# STLINKv2DIY.net
KiCad netlist of a schematic drawn in Altium Designer
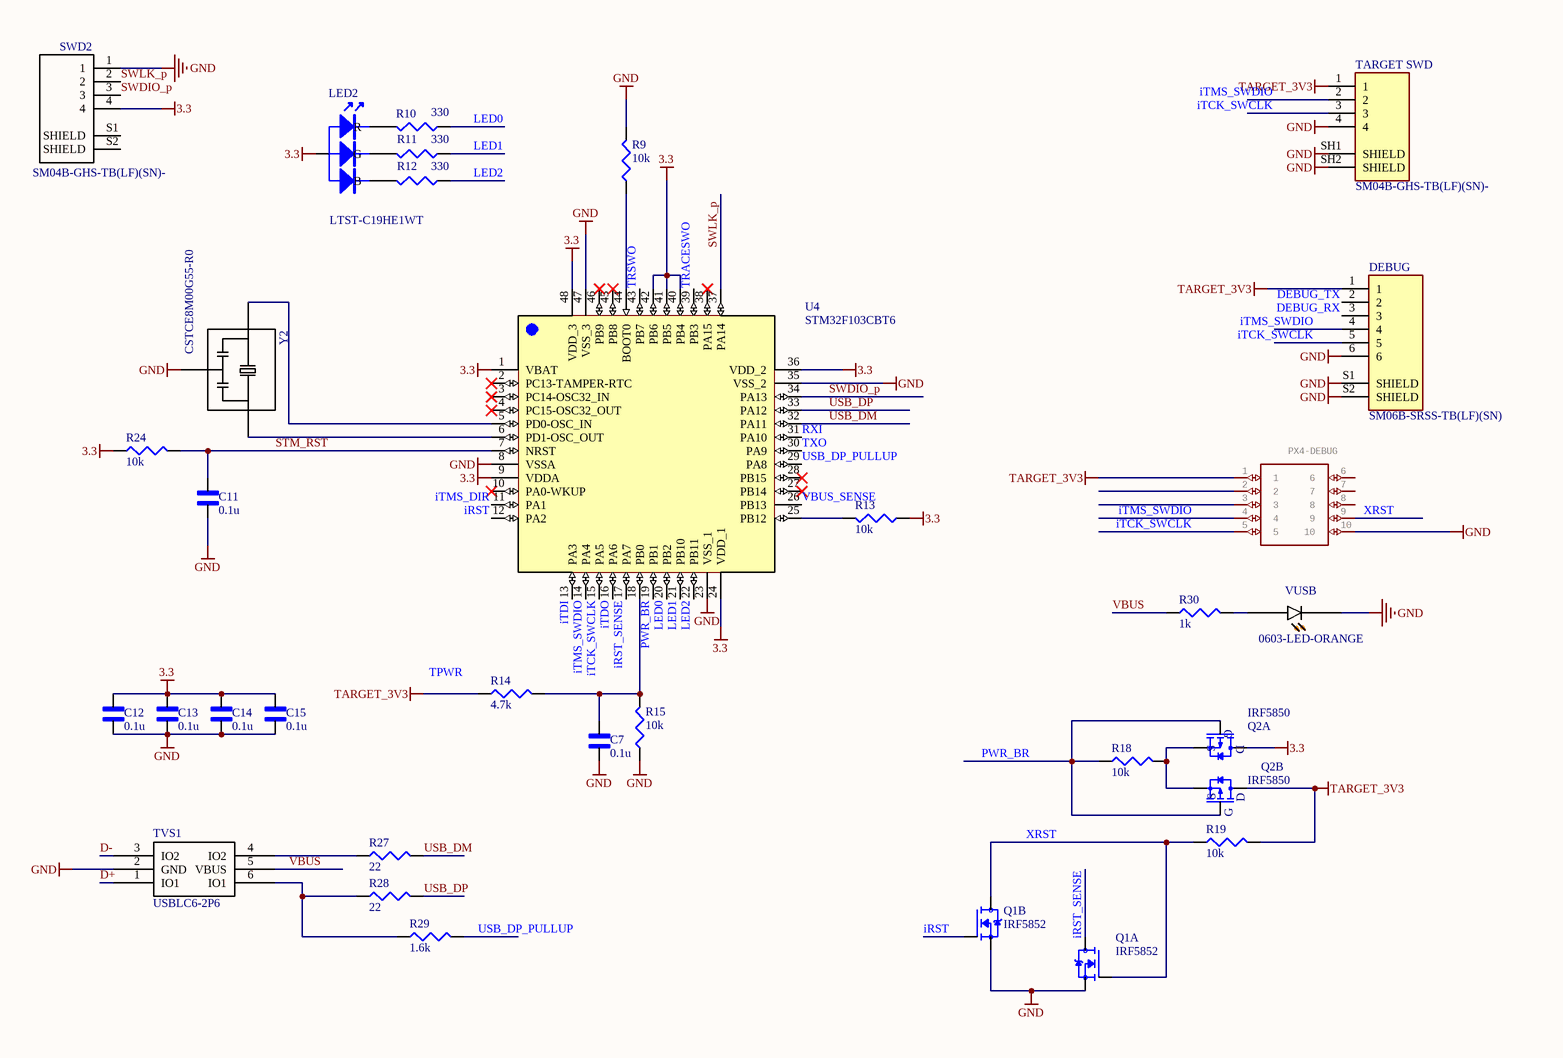
[diagram p0: STLINKv2DIY.SchDoc]

(export (version "E")
  (design (tool "Eeschema 10.0.6"))
  (components
    (comp (ref "C7")
      (value "0.1u")
      (footprint "CAPC1005X55N")
      (description "GCM155R71H104KE02D, Чип 0402 X7R 0.1uF +10% 50V,Конденсатор")
      (fields (field (name "MF") "Murata") (field (name "MP") "GCM155R71H104KE02D"))
      (libsource (lib "lib") (part "GCM155R71H104KE02D"))
    )
    (comp (ref "C11")
      (value "0.1u")
      (footprint "CAPC1005X55N")
      (description "GCM155R71H104KE02D, Чип 0402 X7R 0.1uF +10% 50V,Конденсатор")
      (fields (field (name "MF") "Murata") (field (name "MP") "GCM155R71H104KE02D"))
      (libsource (lib "lib") (part "GCM155R71H104KE02D"))
    )
    (comp (ref "C12")
      (value "0.1u")
      (footprint "CAPC1005X55N")
      (description "GCM155R71H104KE02D, Чип 0402 X7R 0.1uF +10% 50V,Конденсатор")
      (fields (field (name "MF") "Murata") (field (name "MP") "GCM155R71H104KE02D"))
      (libsource (lib "lib") (part "GCM155R71H104KE02D"))
    )
    (comp (ref "C13")
      (value "0.1u")
      (footprint "CAPC1005X55N")
      (description "GCM155R71H104KE02D, Чип 0402 X7R 0.1uF +10% 50V,Конденсатор")
      (fields (field (name "MF") "Murata") (field (name "MP") "GCM155R71H104KE02D"))
      (libsource (lib "lib") (part "GCM155R71H104KE02D"))
    )
    (comp (ref "C14")
      (value "0.1u")
      (footprint "CAPC1005X55N")
      (description "GCM155R71H104KE02D, Чип 0402 X7R 0.1uF +10% 50V,Конденсатор")
      (fields (field (name "MF") "Murata") (field (name "MP") "GCM155R71H104KE02D"))
      (libsource (lib "lib") (part "GCM155R71H104KE02D"))
    )
    (comp (ref "C15")
      (value "0.1u")
      (footprint "CAPC1005X55N")
      (description "GCM155R71H104KE02D, Чип 0402 X7R 0.1uF +10% 50V,Конденсатор")
      (fields (field (name "MF") "Murata") (field (name "MP") "GCM155R71H104KE02D"))
      (libsource (lib "lib") (part "GCM155R71H104KE02D"))
    )
    (comp (ref "DEBUG")
      (value "SM06B-SRSS-TB(LF)(SN)")
      (footprint "JST_SM06B-SRSS-TB(LF)(SN)")
      (description "Connector Header Surface Mount, Right Angle 6 position 0.039 _1.00mm_")
      (fields (field (name "MP") "SM06B-SRSS-TB_LF__SN_") (field (name "MF") "JST Sales"))
      (libsource (lib "lib") (part "SM06B-SRSS-TB(LF)(SN)"))
    )
    (comp (ref "LED2")
      (value "LTST-C19HE1WT")
      (footprint "LTST-C19HE1WT")
      (description "Blue/Green/Red")
      (libsource (lib "lib") (part "RGB_LED_5MM"))
    )
    (comp (ref "PX4-DEBUG")
      (value "JST (JAPAN SOLDERLESS TERMINALS) - SM10B-SRSS-TB(LF)(SN) - HEADER, R/A, 10WAY   Source:  Datasheet")
      (footprint "SM10B-SRSS-TB")
      (fields
        (field (name "MANUFACTURER_PART_NUMBER") "SM10B-SRSS-TB(LF)(SN)")
        (field (name "MP") "SM10B-SRSS-TB")
        (field (name "MF") "JST Sales")
      )
      (libsource (lib "lib") (part "SM10B-SRSS-TB_LF__SN_"))
    )
    (comp (ref "Q1")
      (value "IRF5852")
      (footprint "SOT23-6")
      (description "Mosfet Array 2 N-Channel _Dual_ 20V 2.7A 960mW Surface Mount 6-TSOP")
      (fields (field (name "MF") "Infineon"))
      (libsource (lib "") (part "IRF5852_1"))
    )
    (comp (ref "Q2")
      (value "IRF5850")
      (footprint "SOT23-6")
      (description "Mosfet Array 2 P-Channel (Dual) 20V 2.2A 960mW Surface Mount 6-TSOP")
      (fields (field (name "MF") "Infineon"))
      (libsource (lib "lib") (part "IRF5850"))
    )
    (comp (ref "R9")
      (value "10k")
      (footprint "RESC1005X40N")
      (description "0.062Вт 0402 10 кОм, 1%, Чип резистор (SMD)")
      (fields (field (name "MF") "Yageo or NXP") (field (name "MP") "RC0402FR-0710KL"))
      (libsource (lib "lib") (part "RC0402FR-0710KL"))
    )
    (comp (ref "R10")
      (value "330")
      (footprint "RESC1005X40N")
      (description "0.062Вт 0402 330 Ом, 1%, Чип резистор (SMD)")
      (fields (field (name "MF") "Yageo or NXP") (field (name "MP") "RC0402FR-07330RL"))
      (libsource (lib "lib") (part "RC0402FR-07330RL"))
    )
    (comp (ref "R11")
      (value "330")
      (footprint "RESC1005X40N")
      (description "0.062Вт 0402 330 Ом, 1%, Чип резистор (SMD)")
      (fields (field (name "MF") "Yageo or NXP") (field (name "MP") "RC0402FR-07330RL"))
      (libsource (lib "lib") (part "RC0402FR-07330RL"))
    )
    (comp (ref "R12")
      (value "330")
      (footprint "RESC1005X40N")
      (description "0.062Вт 0402 330 Ом, 1%, Чип резистор (SMD)")
      (fields (field (name "MF") "Yageo or NXP") (field (name "MP") "RC0402FR-07330RL"))
      (libsource (lib "lib") (part "RC0402FR-07330RL"))
    )
    (comp (ref "R13")
      (value "10k")
      (footprint "RESC1005X40N")
      (description "0.062Вт 0402 10 кОм, 1%, Чип резистор (SMD)")
      (fields (field (name "MF") "Yageo or NXP") (field (name "MP") "RC0402FR-0710KL"))
      (libsource (lib "lib") (part "RC0402FR-0710KL"))
    )
    (comp (ref "R14")
      (value "4.7k")
      (footprint "RESC1005X40N")
      (description "0.062Вт 0402 4.7 кОм, 1%, Чип резистор (SMD)")
      (fields (field (name "MF") "Yageo or NXP") (field (name "MP") "RC0402FR-074K7L"))
      (libsource (lib "lib") (part "RC0402FR-074K7L"))
    )
    (comp (ref "R15")
      (value "10k")
      (footprint "RESC1005X40N")
      (description "0.062Вт 0402 10 кОм, 1%, Чип резистор (SMD)")
      (fields (field (name "MF") "Yageo or NXP") (field (name "MP") "RC0402FR-0710KL"))
      (libsource (lib "lib") (part "RC0402FR-0710KL"))
    )
    (comp (ref "R18")
      (value "10k")
      (footprint "RESC1005X40N")
      (description "0.062Вт 0402 10 кОм, 1%, Чип резистор (SMD)")
      (fields (field (name "MF") "Yageo or NXP") (field (name "MP") "RC0402FR-0710KL"))
      (libsource (lib "lib") (part "RC0402FR-0710KL"))
    )
    (comp (ref "R19")
      (value "10k")
      (footprint "RESC1005X40N")
      (description "0.062Вт 0402 10 кОм, 1%, Чип резистор (SMD)")
      (fields (field (name "MF") "Yageo or NXP") (field (name "MP") "RC0402FR-0710KL"))
      (libsource (lib "lib") (part "RC0402FR-0710KL"))
    )
    (comp (ref "R24")
      (value "10k")
      (footprint "RESC1005X40N")
      (description "0.062Вт 0402 10 кОм, 1%, Чип резистор (SMD)")
      (fields (field (name "MF") "Yageo or NXP") (field (name "MP") "RC0402FR-0710KL"))
      (libsource (lib "lib") (part "RC0402FR-0710KL"))
    )
    (comp (ref "R27")
      (value "22")
      (footprint "RESC1005X40N")
      (description "0.062Вт 0402 22 Ом, 1%, Чип резистор (SMD)")
      (fields (field (name "MF") "Yageo or NXP") (field (name "MP") "RC0402FR-0722RL"))
      (libsource (lib "lib") (part "RC0402FR-0722RL"))
    )
    (comp (ref "R28")
      (value "22")
      (footprint "RESC1005X40N")
      (description "0.062Вт 0402 22 Ом, 1%, Чип резистор (SMD)")
      (fields (field (name "MF") "Yageo or NXP") (field (name "MP") "RC0402FR-0722RL"))
      (libsource (lib "lib") (part "RC0402FR-0722RL"))
    )
    (comp (ref "R29")
      (value "1.6k")
      (footprint "RESC1005X40N")
      (description "0.062Вт 0402 1.6 кОм, 1%, Чип резистор (SMD)")
      (fields (field (name "MF") "Yageo or NXP") (field (name "MP") "RC0402FR-071K6L"))
      (libsource (lib "lib") (part "RC0402FR-071K6L"))
    )
    (comp (ref "R30")
      (value "1k")
      (footprint "RESC1005X40N")
      (description "0.062Вт 0402 1 кОм, 1%, Чип резистор (SMD)")
      (fields (field (name "MF") "Yageo or NXP") (field (name "MP") "RC0402FR-071KL"))
      (libsource (lib "lib") (part "RC0402FR-071KL"))
    )
    (comp (ref "SWD2")
      (value "SM04B-GHS-TB(LF)(SN)-")
      (footprint "JST_BM04B-GHS-holes")
      (description "Conn Shrouded Header HDR 4 POS 1.25mm Solder ST SMD Reel")
      (fields (field (name "MF") "JST Sales") (field (name "MP") "SM04B-GHS-TB(LF)(SN)"))
      (libsource (lib "lib") (part "SWD SM04B-GHS-TB(LF)(SN)-"))
    )
    (comp (ref "TARGET SWD")
      (value "SM04B-GHS-TB(LF)(SN)-")
      (footprint "JST_SM04B-GHS-TB(LF)(SN)-")
      (description "Connector Header Surface Mount, Right Angle 4 position 0.049 _1.25mm_")
      (fields (field (name "MP") "SM04B-GHS-TB(LF)(SN)") (field (name "MF") "JST Sales"))
      (libsource (lib "lib") (part "SM04B-GHS-TB(LF)(SN)-"))
    )
    (comp (ref "TVS1")
      (value "USBLC6-2P6")
      (footprint "SOT23127P600-8N")
      (description "17V Clamp 5A (8/20µs) Ipp Tvs Diode Surface Mount SOT-666")
      (fields (field (name "MF") "STM"))
      (libsource (lib "lib") (part "USBLC6-2P6"))
    )
    (comp (ref "U4")
      (value "STM32F103CBT6")
      (footprint "STM-LQFP48_N")
      (description "ARM® Cortex®-M3 STM32F1 Microcontroller IC 32-Bit 72MHz 128KB (128K x 8) FLASH")
      (fields (field (name "MF") "STM"))
      (libsource (lib "lib") (part "STM32F103CBT6"))
    )
    (comp (ref "VUSB")
      (value "0603-LED-ORANGE")
      (footprint "*LEDM1608X80_LTE-C1906R-14(Primary)")
      (description "Orange 605nm LED Indication - Discrete 2.2V 0603 (1608 Metric)")
      (fields (field (name "MP") "LTST-C194KFKT"))
      (libsource (lib "lib") (part "0603-LED-ORANGE"))
    )
    (comp (ref "Y2")
      (value "CSTCE8M00G55-R0")
      (footprint "*OSC_CSTCE8M00G55-R0")
      (description "Ceramic Resonator 8MHz ??0.5% _Tol_ ??0.2% _Stability_ 33pF 40Ohm 3-Pin CSMD T/R")
      (fields (field (name "MF") "Murata"))
      (libsource (lib "lib") (part "CSTCE8M00G55-R0"))
    )
  )
  (nets
    (net (code "1") (name "/D+") (class "Default")
      (node (ref "TVS1") (pin "1") (pinfunction "IO1_1") (pintype "passive"))
    )
    (net (code "2") (name "/D-") (class "Default")
      (node (ref "TVS1") (pin "3") (pinfunction "IO2_3") (pintype "passive"))
    )
    (net (code "3") (name "/DEBUG_RX") (class "Default")
      (node (ref "DEBUG") (pin "3") (pinfunction "3_3") (pintype "passive"))
    )
    (net (code "4") (name "/DEBUG_TX") (class "Default")
      (node (ref "DEBUG") (pin "2") (pinfunction "2_2") (pintype "passive"))
    )
    (net (code "5") (name "/LED0") (class "Default")
      (node (ref "R10") (pin "1") (pinfunction "1_1") (pintype "passive"))
      (node (ref "U4") (pin "20") (pinfunction "PB2_20") (pintype "bidirectional"))
    )
    (net (code "6") (name "/LED1") (class "Default")
      (node (ref "R11") (pin "1") (pinfunction "1_1") (pintype "passive"))
      (node (ref "U4") (pin "21") (pinfunction "PB10_21") (pintype "bidirectional"))
    )
    (net (code "7") (name "/LED2") (class "Default")
      (node (ref "R12") (pin "1") (pinfunction "1_1") (pintype "passive"))
      (node (ref "U4") (pin "22") (pinfunction "PB11_22") (pintype "bidirectional"))
    )
    (net (code "8") (name "/PWR_BR") (class "Default")
      (node (ref "Q2") (pin "1") (pinfunction "G_1") (pintype "passive"))
      (node (ref "Q2") (pin "3") (pinfunction "G_3") (pintype "passive"))
      (node (ref "R18") (pin "1") (pinfunction "1_1") (pintype "passive"))
      (node (ref "U4") (pin "19") (pinfunction "PB1_19") (pintype "bidirectional"))
    )
    (net (code "9") (name "/RXI") (class "Default")
      (node (ref "U4") (pin "31") (pinfunction "PA10_31") (pintype "bidirectional"))
    )
    (net (code "10") (name "/STM_RST") (class "Default")
      (node (ref "C11") (pin "2") (pinfunction "2_2") (pintype "passive"))
      (node (ref "R24") (pin "2") (pinfunction "2_2") (pintype "passive"))
      (node (ref "U4") (pin "7") (pinfunction "NRST_7") (pintype "bidirectional"))
    )
    (net (code "11") (name "/SWDIO_p") (class "Default")
      (node (ref "SWD2") (pin "3") (pinfunction "3_3") (pintype "passive"))
      (node (ref "U4") (pin "34") (pinfunction "PA13_34") (pintype "bidirectional"))
    )
    (net (code "12") (name "/SWLK_p") (class "Default")
      (node (ref "SWD2") (pin "2") (pinfunction "2_2") (pintype "passive"))
      (node (ref "U4") (pin "37") (pinfunction "PA14_37") (pintype "bidirectional"))
    )
    (net (code "14") (name "/TRACESWO") (class "Default")
      (node (ref "U4") (pin "39") (pinfunction "PB3_39") (pintype "bidirectional"))
    )
    (net (code "15") (name "/TRSWO") (class "Default")
      (node (ref "U4") (pin "43") (pinfunction "PB7_43") (pintype "bidirectional"))
    )
    (net (code "16") (name "/TXO") (class "Default")
      (node (ref "U4") (pin "30") (pinfunction "PA9_30") (pintype "bidirectional"))
    )
    (net (code "17") (name "/USB_DM") (class "Default")
      (node (ref "R27") (pin "2") (pinfunction "2_2") (pintype "passive"))
      (node (ref "U4") (pin "32") (pinfunction "PA11_32") (pintype "bidirectional"))
    )
    (net (code "18") (name "/USB_DP") (class "Default")
      (node (ref "R28") (pin "2") (pinfunction "2_2") (pintype "passive"))
      (node (ref "U4") (pin "33") (pinfunction "PA12_33") (pintype "bidirectional"))
    )
    (net (code "19") (name "/USB_DP_PULLUP") (class "Default")
      (node (ref "R29") (pin "2") (pinfunction "2_2") (pintype "passive"))
      (node (ref "U4") (pin "29") (pinfunction "PA8_29") (pintype "bidirectional"))
    )
    (net (code "20") (name "/VBUS") (class "Default")
      (node (ref "R30") (pin "1") (pinfunction "1_1") (pintype "passive"))
      (node (ref "TVS1") (pin "5") (pinfunction "VBUS_5") (pintype "passive"))
    )
    (net (code "21") (name "/VBUS_SENSE") (class "Default")
      (node (ref "U4") (pin "26") (pinfunction "PB13_26") (pintype "power_in"))
    )
    (net (code "22") (name "/XRST") (class "Default")
      (node (ref "PX4-DEBUG") (pin "9") (pinfunction "9_9") (pintype "bidirectional"))
      (node (ref "Q1") (pin "1") (pinfunction "G_1") (pintype "passive"))
      (node (ref "Q1") (pin "4") (pinfunction "D_4") (pintype "passive"))
      (node (ref "R19") (pin "1") (pinfunction "1_1") (pintype "passive"))
    )
    (net (code "23") (name "/iRST") (class "Default")
      (node (ref "Q1") (pin "3") (pinfunction "G_3") (pintype "passive"))
      (node (ref "U4") (pin "12") (pinfunction "PA2_12") (pintype "bidirectional"))
    )
    (net (code "24") (name "/iRST_SENSE") (class "Default")
      (node (ref "Q1") (pin "6") (pinfunction "D_6") (pintype "passive"))
      (node (ref "U4") (pin "17") (pinfunction "PA7_17") (pintype "bidirectional"))
    )
    (net (code "25") (name "/iTCK_SWCLK") (class "Default")
      (node (ref "DEBUG") (pin "5") (pinfunction "5_5") (pintype "passive"))
      (node (ref "PX4-DEBUG") (pin "5") (pinfunction "5_5") (pintype "bidirectional"))
      (node (ref "TARGET SWD") (pin "3") (pinfunction "3_3") (pintype "passive"))
      (node (ref "U4") (pin "15") (pinfunction "PA5_15") (pintype "bidirectional"))
    )
    (net (code "26") (name "/iTDI") (class "Default")
      (node (ref "U4") (pin "13") (pinfunction "PA3_13") (pintype "bidirectional"))
    )
    (net (code "27") (name "/iTDO") (class "Default")
      (node (ref "U4") (pin "16") (pinfunction "PA6_16") (pintype "bidirectional"))
    )
    (net (code "28") (name "/iTMS_DIR") (class "Default")
      (node (ref "U4") (pin "11") (pinfunction "PA1_11") (pintype "bidirectional"))
    )
    (net (code "29") (name "/iTMS_SWDIO") (class "Default")
      (node (ref "DEBUG") (pin "4") (pinfunction "4_4") (pintype "passive"))
      (node (ref "PX4-DEBUG") (pin "4") (pinfunction "4_4") (pintype "bidirectional"))
      (node (ref "TARGET SWD") (pin "2") (pinfunction "2_2") (pintype "passive"))
      (node (ref "U4") (pin "14") (pinfunction "PA4_14") (pintype "bidirectional"))
    )
    (net (code "30") (name "3.3") (class "Default")
      (node (ref "C12") (pin "2") (pinfunction "2_2") (pintype "passive"))
      (node (ref "C13") (pin "2") (pinfunction "2_2") (pintype "passive"))
      (node (ref "C14") (pin "2") (pinfunction "2_2") (pintype "passive"))
      (node (ref "C15") (pin "2") (pinfunction "2_2") (pintype "passive"))
      (node (ref "LED2") (pin "4") (pinfunction "A_4") (pintype "passive"))
      (node (ref "Q2") (pin "6") (pinfunction "D_6") (pintype "passive"))
      (node (ref "R13") (pin "1") (pinfunction "1_1") (pintype "passive"))
      (node (ref "R24") (pin "1") (pinfunction "1_1") (pintype "passive"))
      (node (ref "SWD2") (pin "4") (pinfunction "4_4") (pintype "passive"))
      (node (ref "U4") (pin "1") (pinfunction "VBAT_1") (pintype "power_in"))
      (node (ref "U4") (pin "24") (pinfunction "VDD_1_24") (pintype "power_in"))
      (node (ref "U4") (pin "36") (pinfunction "VDD_2_36") (pintype "power_in"))
      (node (ref "U4") (pin "40") (pinfunction "PB4_40") (pintype "bidirectional"))
      (node (ref "U4") (pin "41") (pinfunction "PB5_41") (pintype "bidirectional"))
      (node (ref "U4") (pin "42") (pinfunction "PB6_42") (pintype "bidirectional"))
      (node (ref "U4") (pin "48") (pinfunction "VDD_3_48") (pintype "power_in"))
      (node (ref "U4") (pin "9") (pinfunction "VDDA_9") (pintype "power_in"))
    )
    (net (code "31") (name "GND") (class "Default")
      (node (ref "C11") (pin "1") (pinfunction "1_1") (pintype "passive"))
      (node (ref "C12") (pin "1") (pinfunction "1_1") (pintype "passive"))
      (node (ref "C13") (pin "1") (pinfunction "1_1") (pintype "passive"))
      (node (ref "C14") (pin "1") (pinfunction "1_1") (pintype "passive"))
      (node (ref "C15") (pin "1") (pinfunction "1_1") (pintype "passive"))
      (node (ref "C7") (pin "1") (pinfunction "1_1") (pintype "passive"))
      (node (ref "DEBUG") (pin "6") (pinfunction "6_6") (pintype "passive"))
      (node (ref "DEBUG") (pin "S1") (pinfunction "SHIELD_S1") (pintype "passive"))
      (node (ref "DEBUG") (pin "S2") (pinfunction "SHIELD_S2") (pintype "passive"))
      (node (ref "PX4-DEBUG") (pin "10") (pinfunction "10_10") (pintype "bidirectional"))
      (node (ref "Q1") (pin "2") (pinfunction "S_2") (pintype "passive"))
      (node (ref "Q1") (pin "5") (pinfunction "S_5") (pintype "passive"))
      (node (ref "R15") (pin "1") (pinfunction "1_1") (pintype "passive"))
      (node (ref "R9") (pin "2") (pinfunction "2_2") (pintype "passive"))
      (node (ref "SWD2") (pin "1") (pinfunction "1_1") (pintype "passive"))
      (node (ref "TARGET SWD") (pin "4") (pinfunction "4_4") (pintype "passive"))
      (node (ref "TARGET SWD") (pin "SH1") (pinfunction "SHIELD_SH1") (pintype "power_in"))
      (node (ref "TARGET SWD") (pin "SH2") (pinfunction "SHIELD_SH2") (pintype "power_in"))
      (node (ref "TVS1") (pin "2") (pinfunction "GND_2") (pintype "passive"))
      (node (ref "U4") (pin "23") (pinfunction "VSS_1_23") (pintype "power_in"))
      (node (ref "U4") (pin "35") (pinfunction "VSS_2_35") (pintype "power_in"))
      (node (ref "U4") (pin "47") (pinfunction "VSS_3_47") (pintype "power_in"))
      (node (ref "U4") (pin "8") (pinfunction "VSSA_8") (pintype "power_in"))
      (node (ref "VUSB") (pin "C") (pinfunction "C_C") (pintype "passive"))
      (node (ref "Y2") (pin "2") (pinfunction "2_2") (pintype "power_in"))
    )
    (net (code "32") (name "Net-(LED2-B)") (class "Default")
      (node (ref "LED2") (pin "3") (pinfunction "B_3") (pintype "passive"))
      (node (ref "R12") (pin "2") (pinfunction "2_2") (pintype "passive"))
    )
    (net (code "33") (name "Net-(LED2-G)") (class "Default")
      (node (ref "LED2") (pin "2") (pinfunction "G_2") (pintype "passive"))
      (node (ref "R11") (pin "2") (pinfunction "2_2") (pintype "passive"))
    )
    (net (code "34") (name "Net-(LED2-R)") (class "Default")
      (node (ref "LED2") (pin "1") (pinfunction "R_1") (pintype "passive"))
      (node (ref "R10") (pin "2") (pinfunction "2_2") (pintype "passive"))
    )
    (net (code "35") (name "Net-(Q2A-S)") (class "Default")
      (node (ref "Q2") (pin "2") (pinfunction "S_2") (pintype "passive"))
      (node (ref "Q2") (pin "5") (pinfunction "S_5") (pintype "passive"))
      (node (ref "R18") (pin "2") (pinfunction "2_2") (pintype "passive"))
    )
    (net (code "36") (name "Net-(R27-Pad1)") (class "Default")
      (node (ref "R27") (pin "1") (pinfunction "1_1") (pintype "passive"))
      (node (ref "TVS1") (pin "4") (pinfunction "IO2_4") (pintype "passive"))
    )
    (net (code "37") (name "Net-(R28-Pad1)") (class "Default")
      (node (ref "R28") (pin "1") (pinfunction "1_1") (pintype "passive"))
      (node (ref "R29") (pin "1") (pinfunction "1_1") (pintype "passive"))
      (node (ref "TVS1") (pin "6") (pinfunction "IO1_6") (pintype "passive"))
    )
    (net (code "38") (name "Net-(R30-Pad2)") (class "Default")
      (node (ref "R30") (pin "2") (pinfunction "2_2") (pintype "passive"))
      (node (ref "VUSB") (pin "A") (pinfunction "A_A") (pintype "passive"))
    )
    (net (code "39") (name "Net-(U4-BOOT0)") (class "Default")
      (node (ref "R9") (pin "1") (pinfunction "1_1") (pintype "passive"))
      (node (ref "U4") (pin "44") (pinfunction "BOOT0_44") (pintype "input"))
    )
    (net (code "40") (name "Net-(U4-PB0)") (class "Default")
      (node (ref "C7") (pin "2") (pinfunction "2_2") (pintype "passive"))
      (node (ref "R14") (pin "2") (pinfunction "2_2") (pintype "passive"))
      (node (ref "R15") (pin "2") (pinfunction "2_2") (pintype "passive"))
      (node (ref "U4") (pin "18") (pinfunction "PB0_18") (pintype "bidirectional"))
    )
    (net (code "41") (name "Net-(U4-PB12)") (class "Default")
      (node (ref "R13") (pin "2") (pinfunction "2_2") (pintype "passive"))
      (node (ref "U4") (pin "25") (pinfunction "PB12_25") (pintype "bidirectional"))
    )
    (net (code "42") (name "Net-(U4-PD0-OSC_IN)") (class "Default")
      (node (ref "U4") (pin "5") (pinfunction "PD0-OSC_IN_5") (pintype "bidirectional"))
      (node (ref "Y2") (pin "1") (pinfunction "1_1") (pintype "passive"))
    )
    (net (code "43") (name "Net-(U4-PD1-OSC_OUT)") (class "Default")
      (node (ref "U4") (pin "6") (pinfunction "PD1-OSC_OUT_6") (pintype "bidirectional"))
      (node (ref "Y2") (pin "3") (pinfunction "3_3") (pintype "passive"))
    )
    (net (code "44") (name "TARGET_3V3") (class "Default")
      (node (ref "DEBUG") (pin "1") (pinfunction "1_1") (pintype "passive"))
      (node (ref "PX4-DEBUG") (pin "1") (pinfunction "1_1") (pintype "bidirectional"))
      (node (ref "Q2") (pin "4") (pinfunction "D_4") (pintype "passive"))
      (node (ref "R14") (pin "1") (pinfunction "1_1") (pintype "passive"))
      (node (ref "R19") (pin "2") (pinfunction "2_2") (pintype "passive"))
      (node (ref "TARGET SWD") (pin "1") (pinfunction "1_1") (pintype "passive"))
    )
    (net (code "45") (name "unconnected-(PX4-DEBUG-Pad2)") (class "Default")
      (node (ref "PX4-DEBUG") (pin "2") (pinfunction "2_2") (pintype "bidirectional"))
    )
    (net (code "46") (name "unconnected-(PX4-DEBUG-Pad3)") (class "Default")
      (node (ref "PX4-DEBUG") (pin "3") (pinfunction "3_3") (pintype "bidirectional"))
    )
    (net (code "47") (name "unconnected-(PX4-DEBUG-Pad6)") (class "Default")
      (node (ref "PX4-DEBUG") (pin "6") (pinfunction "6_6") (pintype "bidirectional"))
    )
    (net (code "48") (name "unconnected-(PX4-DEBUG-Pad7)") (class "Default")
      (node (ref "PX4-DEBUG") (pin "7") (pinfunction "7_7") (pintype "bidirectional"))
    )
    (net (code "49") (name "unconnected-(PX4-DEBUG-Pad8)") (class "Default")
      (node (ref "PX4-DEBUG") (pin "8") (pinfunction "8_8") (pintype "bidirectional"))
    )
    (net (code "50") (name "unconnected-(SWD2-SHIELD-PadS1)") (class "Default")
      (node (ref "SWD2") (pin "S1") (pinfunction "SHIELD_S1") (pintype "passive"))
    )
    (net (code "51") (name "unconnected-(SWD2-SHIELD-PadS2)") (class "Default")
      (node (ref "SWD2") (pin "S2") (pinfunction "SHIELD_S2") (pintype "passive"))
    )
    (net (code "52") (name "unconnected-(U4-PA0-WKUP-Pad10)") (class "Default")
      (node (ref "U4") (pin "10") (pinfunction "PA0-WKUP_10") (pintype "bidirectional+no_connect"))
    )
    (net (code "53") (name "unconnected-(U4-PA15-Pad38)") (class "Default")
      (node (ref "U4") (pin "38") (pinfunction "PA15_38") (pintype "bidirectional+no_connect"))
    )
    (net (code "54") (name "unconnected-(U4-PB8-Pad45)") (class "Default")
      (node (ref "U4") (pin "45") (pinfunction "PB8_45") (pintype "bidirectional+no_connect"))
    )
    (net (code "55") (name "unconnected-(U4-PB9-Pad46)") (class "Default")
      (node (ref "U4") (pin "46") (pinfunction "PB9_46") (pintype "bidirectional+no_connect"))
    )
    (net (code "56") (name "unconnected-(U4-PB14-Pad27)") (class "Default")
      (node (ref "U4") (pin "27") (pinfunction "PB14_27") (pintype "bidirectional+no_connect"))
    )
    (net (code "57") (name "unconnected-(U4-PB15-Pad28)") (class "Default")
      (node (ref "U4") (pin "28") (pinfunction "PB15_28") (pintype "bidirectional+no_connect"))
    )
    (net (code "58") (name "unconnected-(U4-PC13-TAMPER-RTC-Pad2)") (class "Default")
      (node (ref "U4") (pin "2") (pinfunction "PC13-TAMPER-RTC_2") (pintype "bidirectional+no_connect"))
    )
    (net (code "59") (name "unconnected-(U4-PC14-OSC32_IN-Pad3)") (class "Default")
      (node (ref "U4") (pin "3") (pinfunction "PC14-OSC32_IN_3") (pintype "bidirectional+no_connect"))
    )
    (net (code "60") (name "unconnected-(U4-PC15-OSC32_OUT-Pad4)") (class "Default")
      (node (ref "U4") (pin "4") (pinfunction "PC15-OSC32_OUT_4") (pintype "bidirectional+no_connect"))
    )
  )
)
